# flexPCB.net
KiCad netlist of a schematic drawn in Altium Designer
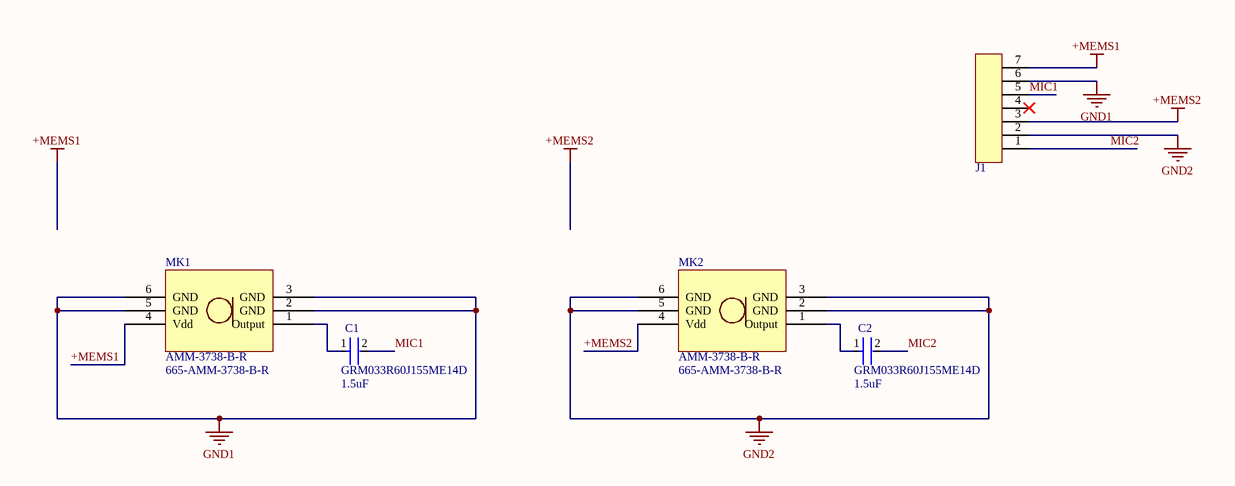
[diagram p0: flexPCB.SchDoc]

(export (version "E")
  (design (tool "Eeschema 10.0.6"))
  (components
    (comp (ref "C1")
      (value "GRM033R60J155ME14D")
      (footprint "FP-GRM033-0_03-IPC_B")
      (description "Chip Multilayer Ceramic Capacitors for General Purpose, 0201, 1.5uF, X5R, 15%, 20%, 6.3V")
      (fields (field (name "TOLERANCE") "20%"))
      (libsource (lib "Altium Content Vault") (part "b4654b650e69147ec39a6b967a45e02"))
    )
    (comp (ref "C2")
      (value "GRM033R60J155ME14D")
      (footprint "FP-GRM033-0_03-IPC_B")
      (description "Chip Multilayer Ceramic Capacitors for General Purpose, 0201, 1.5uF, X5R, 15%, 20%, 6.3V")
      (fields (field (name "TOLERANCE") "20%"))
      (libsource (lib "Altium Content Vault") (part "b4654b650e69147ec39a6b967a45e02"))
    )
    (comp (ref "J1")
      (value "FFC EDGE BOTTOM")
      (footprint "HIROSE_FH58M-7S-0.25SHW-99_BOTTOMFFC")
      (description "Bottom FFC Land Pattern for Hirose FH58M-7S-0.25SHW(99) 7-pin Top+Bottom Contact FFC Connector")
      (libsource (lib "OSP_Symbols") (part "HIROSE_FH58M-7S-0.25SHW-99_BOTTOM"))
    )
    (comp (ref "MK1")
      (value "AMM-3738-B-R")
      (footprint "665-AMM-3738-B-R")
      (fields
        (field (name "MANUFACTURER") "PUI Audio")
        (field (name "SUPPLIER PART NUMBER 1") "665-AMM-3738-B-R")
      )
      (libsource (lib "Analog_mic_breakout") (part "AMM-3738-B-R"))
    )
    (comp (ref "MK2")
      (value "AMM-3738-B-R")
      (footprint "665-AMM-3738-B-R")
      (fields
        (field (name "MANUFACTURER") "PUI Audio")
        (field (name "SUPPLIER PART NUMBER 1") "665-AMM-3738-B-R")
      )
      (libsource (lib "Analog_mic_breakout") (part "AMM-3738-B-R"))
    )
  )
  (nets
    (net (code "1") (name "+MEMS1") (class "Default")
      (node (ref "J1") (pin "7") (pintype "passive"))
      (node (ref "MK1") (pin "4") (pinfunction "Vdd_4") (pintype "power_in"))
    )
    (net (code "2") (name "+MEMS2") (class "Default")
      (node (ref "J1") (pin "3") (pintype "passive"))
      (node (ref "MK2") (pin "4") (pinfunction "Vdd_4") (pintype "power_in"))
    )
    (net (code "3") (name "/MIC1") (class "Default")
      (node (ref "C1") (pin "2") (pinfunction "2_2") (pintype "passive"))
      (node (ref "J1") (pin "5") (pintype "passive"))
    )
    (net (code "4") (name "/MIC2") (class "Default")
      (node (ref "C2") (pin "2") (pinfunction "2_2") (pintype "passive"))
      (node (ref "J1") (pin "1") (pintype "passive"))
    )
    (net (code "5") (name "GND1") (class "Default")
      (node (ref "J1") (pin "6") (pintype "passive"))
      (node (ref "MK1") (pin "2") (pinfunction "GND_2") (pintype "power_in"))
      (node (ref "MK1") (pin "3") (pinfunction "GND_3") (pintype "power_in"))
      (node (ref "MK1") (pin "5") (pinfunction "GND_5") (pintype "power_in"))
      (node (ref "MK1") (pin "6") (pinfunction "GND_6") (pintype "power_in"))
    )
    (net (code "6") (name "GND2") (class "Default")
      (node (ref "J1") (pin "2") (pintype "passive"))
      (node (ref "MK2") (pin "2") (pinfunction "GND_2") (pintype "power_in"))
      (node (ref "MK2") (pin "3") (pinfunction "GND_3") (pintype "power_in"))
      (node (ref "MK2") (pin "5") (pinfunction "GND_5") (pintype "power_in"))
      (node (ref "MK2") (pin "6") (pinfunction "GND_6") (pintype "power_in"))
    )
    (net (code "7") (name "Net-(MK1-Output)") (class "Default")
      (node (ref "C1") (pin "1") (pinfunction "1_1") (pintype "passive"))
      (node (ref "MK1") (pin "1") (pinfunction "Output_1") (pintype "passive"))
    )
    (net (code "8") (name "Net-(MK2-Output)") (class "Default")
      (node (ref "C2") (pin "1") (pinfunction "1_1") (pintype "passive"))
      (node (ref "MK2") (pin "1") (pinfunction "Output_1") (pintype "passive"))
    )
    (net (code "9") (name "unconnected-(J1-Pad4)") (class "Default")
      (node (ref "J1") (pin "4") (pintype "passive+no_connect"))
    )
  )
)
